# arduino_to_bluetooth_hm-10.net
KiCad netlist of a schematic drawn in EAGLE
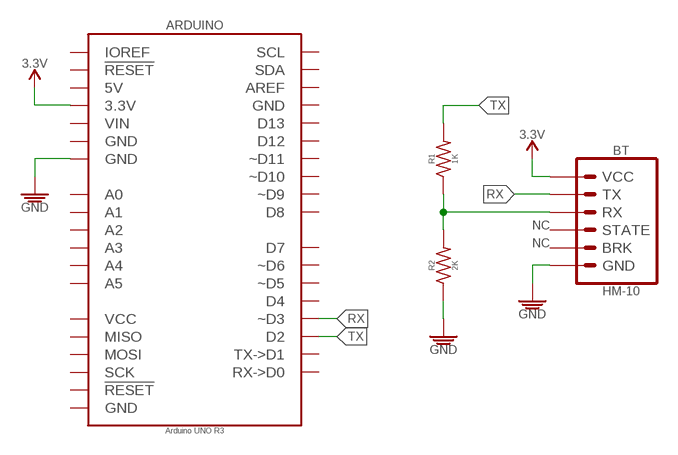
[diagram p0: schematic, sheet 1]

(export (version "E")
  (design (tool "Eeschema 10.0.6"))
  (components
    (comp (ref "ARDUINO")
      (value "Arduino UNO R3")
      (footprint "eagle-import:ARDUINO_UNO_R3")
      (fields (field (name "MFR") "Arduino") (field (name "MPN") "A000066"))
      (libsource (lib "eagle-import") (part "ARDUINO_UNO_R3"))
    )
    (comp (ref "BT")
      (value "HM-10")
      (footprint "eagle-import:1X06-RA-FEMALE_CONNECTOR_BLUETOOTH_HM-10")
      (fields (field (name "MFR") "JNHuaMao Technology Company "))
      (libsource (lib "eagle-import") (part "BLUETOOTH_HM-101X06-RA-FEMALE"))
    )
    (comp (ref "R1")
      (value "1K")
      (footprint "eagle-import:RESISTOR-PTH-0207_7")
      (fields (field (name "MFR") "Yageo") (field (name "MPN") "CFR-25JB-52-1K"))
      (libsource (lib "eagle-import") (part "1KΩ_PTH-0207/7_1/4W-5%"))
    )
    (comp (ref "R2")
      (value "2K")
      (footprint "eagle-import:RESISTOR-PTH-0207_7")
      (fields (field (name "MFR") "Yageo") (field (name "MPN") "CFR-25JB-52-2K"))
      (libsource (lib "eagle-import") (part "2KΩ_PTH-0207/7_1/4W-5%"))
    )
  )
  (nets
    (net (code "1") (name "3.3V") (class "Default")
      (node (ref "ARDUINO") (pin "3.3V") (pinfunction "3.3V_3.3V") (pintype "bidirectional"))
      (node (ref "BT") (pin "RX") (pinfunction "VCC_RX") (pintype "power_in"))
    )
    (net (code "2") (name "GND") (class "Default")
      (node (ref "ARDUINO") (pin "GND@3") (pinfunction "GND_GND@3") (pintype "bidirectional"))
      (node (ref "BT") (pin "TX") (pinfunction "GND_TX") (pintype "power_in"))
      (node (ref "R2") (pin "1") (pinfunction "1_1") (pintype "passive"))
    )
    (net (code "3") (name "RX") (class "Default")
      (node (ref "ARDUINO") (pin "D3") (pinfunction "~{D3}_D3") (pintype "bidirectional"))
      (node (ref "BT") (pin "GND") (pinfunction "TX_GND") (pintype "output"))
      (node (ref "BT") (pin "VCC") (pinfunction "RX_VCC") (pintype "input"))
      (node (ref "R1") (pin "1") (pinfunction "1_1") (pintype "passive"))
      (node (ref "R2") (pin "2") (pinfunction "2_2") (pintype "passive"))
    )
    (net (code "4") (name "TX") (class "Default")
      (node (ref "ARDUINO") (pin "D2") (pinfunction "D2_D2") (pintype "bidirectional"))
      (node (ref "R1") (pin "2") (pinfunction "2_2") (pintype "passive"))
    )
    (net (code "5") (name "unconnected-(ARDUINO-GND-PadGND@1)") (class "Default")
      (node (ref "ARDUINO") (pin "GND@1") (pinfunction "GND_GND@1") (pintype "bidirectional"))
    )
    (net (code "6") (name "unconnected-(ARDUINO-GND-PadGND@2)") (class "Default")
      (node (ref "ARDUINO") (pin "GND@2") (pinfunction "GND_GND@2") (pintype "bidirectional"))
    )
    (net (code "7") (name "unconnected-(ARDUINO-GND-PadGND@4)") (class "Default")
      (node (ref "ARDUINO") (pin "GND@4") (pinfunction "GND_GND@4") (pintype "bidirectional"))
    )
    (net (code "8") (name "unconnected-(ARDUINO-Pad5V)") (class "Default")
      (node (ref "ARDUINO") (pin "5V") (pinfunction "5V_5V") (pintype "bidirectional"))
    )
    (net (code "9") (name "unconnected-(ARDUINO-PadA0)") (class "Default")
      (node (ref "ARDUINO") (pin "A0") (pinfunction "A0_A0") (pintype "bidirectional"))
    )
    (net (code "10") (name "unconnected-(ARDUINO-PadA1)") (class "Default")
      (node (ref "ARDUINO") (pin "A1") (pinfunction "A1_A1") (pintype "bidirectional"))
    )
    (net (code "11") (name "unconnected-(ARDUINO-PadA2)") (class "Default")
      (node (ref "ARDUINO") (pin "A2") (pinfunction "A2_A2") (pintype "bidirectional"))
    )
    (net (code "12") (name "unconnected-(ARDUINO-PadA3)") (class "Default")
      (node (ref "ARDUINO") (pin "A3") (pinfunction "A3_A3") (pintype "bidirectional"))
    )
    (net (code "13") (name "unconnected-(ARDUINO-PadA4)") (class "Default")
      (node (ref "ARDUINO") (pin "A4") (pinfunction "A4_A4") (pintype "bidirectional"))
    )
    (net (code "14") (name "unconnected-(ARDUINO-PadA5)") (class "Default")
      (node (ref "ARDUINO") (pin "A5") (pinfunction "A5_A5") (pintype "bidirectional"))
    )
    (net (code "15") (name "unconnected-(ARDUINO-PadAREF)") (class "Default")
      (node (ref "ARDUINO") (pin "AREF") (pinfunction "AREF_AREF") (pintype "bidirectional"))
    )
    (net (code "16") (name "unconnected-(ARDUINO-PadD4)") (class "Default")
      (node (ref "ARDUINO") (pin "D4") (pinfunction "D4_D4") (pintype "bidirectional"))
    )
    (net (code "17") (name "unconnected-(ARDUINO-PadD7)") (class "Default")
      (node (ref "ARDUINO") (pin "D7") (pinfunction "D7_D7") (pintype "bidirectional"))
    )
    (net (code "18") (name "unconnected-(ARDUINO-PadD8)") (class "Default")
      (node (ref "ARDUINO") (pin "D8") (pinfunction "D8_D8") (pintype "bidirectional"))
    )
    (net (code "19") (name "unconnected-(ARDUINO-PadD12)") (class "Default")
      (node (ref "ARDUINO") (pin "D12") (pinfunction "D12_D12") (pintype "bidirectional"))
    )
    (net (code "20") (name "unconnected-(ARDUINO-PadD13)") (class "Default")
      (node (ref "ARDUINO") (pin "D13") (pinfunction "D13_D13") (pintype "bidirectional"))
    )
    (net (code "21") (name "unconnected-(ARDUINO-PadIOREF)") (class "Default")
      (node (ref "ARDUINO") (pin "IOREF") (pinfunction "IOREF_IOREF") (pintype "bidirectional"))
    )
    (net (code "22") (name "unconnected-(ARDUINO-PadMISO)") (class "Default")
      (node (ref "ARDUINO") (pin "MISO") (pinfunction "MISO_MISO") (pintype "bidirectional"))
    )
    (net (code "23") (name "unconnected-(ARDUINO-PadMOSI)") (class "Default")
      (node (ref "ARDUINO") (pin "MOSI") (pinfunction "MOSI_MOSI") (pintype "bidirectional"))
    )
    (net (code "24") (name "unconnected-(ARDUINO-PadSCK)") (class "Default")
      (node (ref "ARDUINO") (pin "SCK") (pinfunction "SCK_SCK") (pintype "bidirectional"))
    )
    (net (code "25") (name "unconnected-(ARDUINO-PadSCL)") (class "Default")
      (node (ref "ARDUINO") (pin "SCL") (pinfunction "SCL_SCL") (pintype "bidirectional"))
    )
    (net (code "26") (name "unconnected-(ARDUINO-PadSDA)") (class "Default")
      (node (ref "ARDUINO") (pin "SDA") (pinfunction "SDA_SDA") (pintype "bidirectional"))
    )
    (net (code "27") (name "unconnected-(ARDUINO-PadVCC)") (class "Default")
      (node (ref "ARDUINO") (pin "VCC") (pinfunction "VCC_VCC") (pintype "bidirectional"))
    )
    (net (code "28") (name "unconnected-(ARDUINO-PadVIN)") (class "Default")
      (node (ref "ARDUINO") (pin "VIN") (pinfunction "VIN_VIN") (pintype "bidirectional"))
    )
    (net (code "29") (name "unconnected-(ARDUINO-RX->D0-PadD0)") (class "Default")
      (node (ref "ARDUINO") (pin "D0") (pinfunction "RX->D0_D0") (pintype "bidirectional"))
    )
    (net (code "30") (name "unconnected-(ARDUINO-TX->D1-PadD1)") (class "Default")
      (node (ref "ARDUINO") (pin "D1") (pinfunction "TX->D1_D1") (pintype "bidirectional"))
    )
    (net (code "31") (name "unconnected-(ARDUINO-~{D5}-PadD5)") (class "Default")
      (node (ref "ARDUINO") (pin "D5") (pinfunction "~{D5}_D5") (pintype "bidirectional"))
    )
    (net (code "32") (name "unconnected-(ARDUINO-~{D6}-PadD6)") (class "Default")
      (node (ref "ARDUINO") (pin "D6") (pinfunction "~{D6}_D6") (pintype "bidirectional"))
    )
    (net (code "33") (name "unconnected-(ARDUINO-~{D9}-PadD9)") (class "Default")
      (node (ref "ARDUINO") (pin "D9") (pinfunction "~{D9}_D9") (pintype "bidirectional"))
    )
    (net (code "34") (name "unconnected-(ARDUINO-~{D10}-PadD10)") (class "Default")
      (node (ref "ARDUINO") (pin "D10") (pinfunction "~{D10}_D10") (pintype "bidirectional"))
    )
    (net (code "35") (name "unconnected-(ARDUINO-~{D11}-PadD11)") (class "Default")
      (node (ref "ARDUINO") (pin "D11") (pinfunction "~{D11}_D11") (pintype "bidirectional"))
    )
    (net (code "36") (name "unconnected-(ARDUINO-~{RESET}-PadRESET@1)") (class "Default")
      (node (ref "ARDUINO") (pin "RESET@1") (pinfunction "~{RESET}_RESET@1") (pintype "bidirectional"))
    )
    (net (code "37") (name "unconnected-(ARDUINO-~{RESET}-PadRESET@2)") (class "Default")
      (node (ref "ARDUINO") (pin "RESET@2") (pinfunction "~{RESET}_RESET@2") (pintype "bidirectional"))
    )
    (net (code "38") (name "unconnected-(BT-PadBRK)") (class "Default")
      (node (ref "BT") (pin "BRK") (pinfunction "BRK_BRK") (pintype "no_connect"))
    )
    (net (code "39") (name "unconnected-(BT-PadSTATE)") (class "Default")
      (node (ref "BT") (pin "STATE") (pinfunction "STATE_STATE") (pintype "no_connect"))
    )
  )
)
